# Target_board.net
KiCad netlist of a schematic drawn in EAGLE
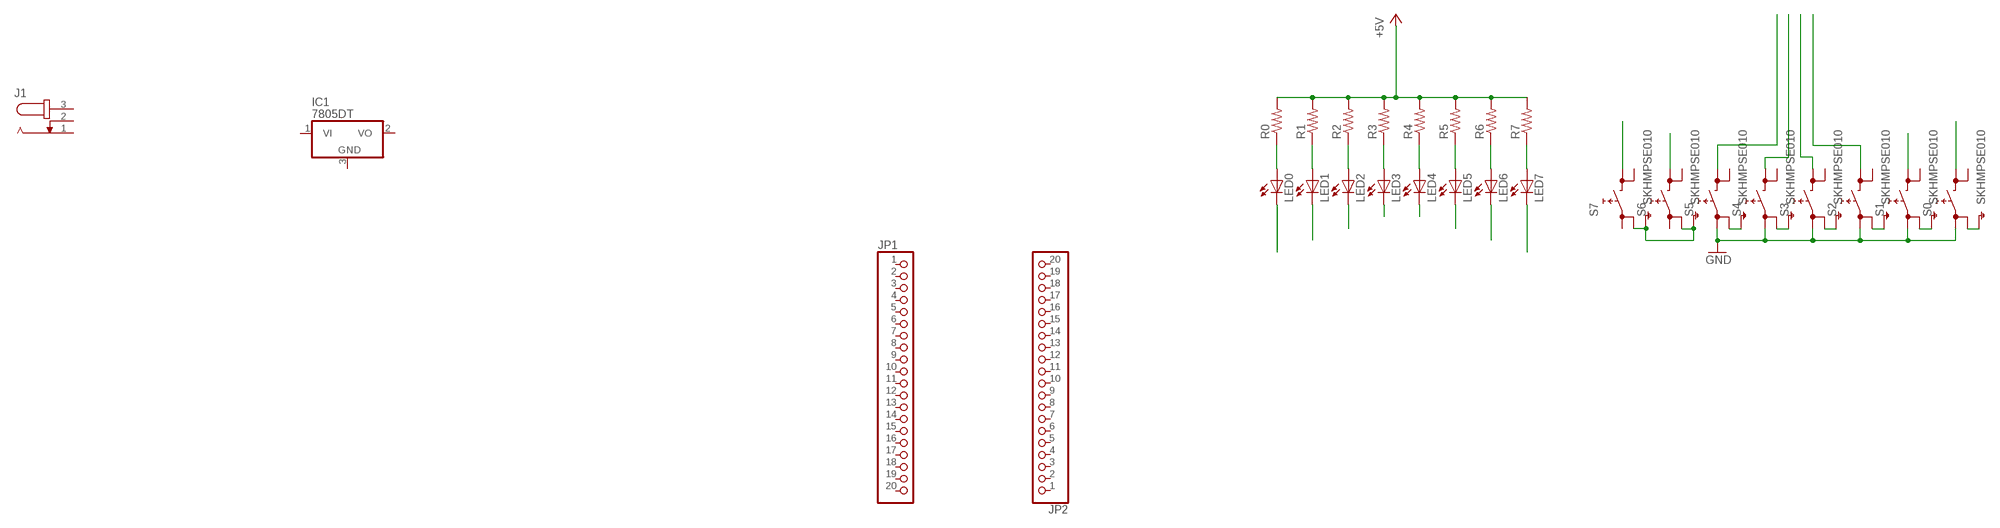
[diagram p0: schematic, sheet 1]

(export (version "E")
  (design (tool "Eeschema 10.0.6"))
  (components
    (comp (ref "IC1")
      (value "7805DT")
      (footprint "eagle-import:TO252")
      (libsource (lib "eagle-import") (part "78DT05"))
    )
    (comp (ref "J1")
      (value "JACK-PLUG0")
      (footprint "eagle-import:SPC4077")
      (libsource (lib "eagle-import") (part "JACK-PLUG0"))
    )
    (comp (ref "JP1")
      (value "PINHD-1X20")
      (footprint "eagle-import:1X20")
      (libsource (lib "eagle-import") (part "PINHD-1X20"))
    )
    (comp (ref "JP2")
      (value "PINHD-1X20")
      (footprint "eagle-import:1X20")
      (libsource (lib "eagle-import") (part "PINHD-1X20"))
    )
    (comp (ref "LED0")
      (value "LEDCHIP-LED0805")
      (footprint "eagle-import:CHIP-LED0805")
      (libsource (lib "eagle-import") (part "LEDCHIP-LED0805"))
    )
    (comp (ref "LED1")
      (value "LEDCHIP-LED0805")
      (footprint "eagle-import:CHIP-LED0805")
      (libsource (lib "eagle-import") (part "LEDCHIP-LED0805"))
    )
    (comp (ref "LED2")
      (value "LEDCHIP-LED0805")
      (footprint "eagle-import:CHIP-LED0805")
      (libsource (lib "eagle-import") (part "LEDCHIP-LED0805"))
    )
    (comp (ref "LED3")
      (value "LEDCHIP-LED0805")
      (footprint "eagle-import:CHIP-LED0805")
      (libsource (lib "eagle-import") (part "LEDCHIP-LED0805"))
    )
    (comp (ref "LED4")
      (value "LEDCHIP-LED0805")
      (footprint "eagle-import:CHIP-LED0805")
      (libsource (lib "eagle-import") (part "LEDCHIP-LED0805"))
    )
    (comp (ref "LED5")
      (value "LEDCHIP-LED0805")
      (footprint "eagle-import:CHIP-LED0805")
      (libsource (lib "eagle-import") (part "LEDCHIP-LED0805"))
    )
    (comp (ref "LED6")
      (value "LEDCHIP-LED0805")
      (footprint "eagle-import:CHIP-LED0805")
      (libsource (lib "eagle-import") (part "LEDCHIP-LED0805"))
    )
    (comp (ref "LED7")
      (value "LEDCHIP-LED0805")
      (footprint "eagle-import:CHIP-LED0805")
      (libsource (lib "eagle-import") (part "LEDCHIP-LED0805"))
    )
    (comp (ref "R0")
      (value "R-US_R0805")
      (footprint "eagle-import:R0805")
      (libsource (lib "eagle-import") (part "R-US_R0805"))
    )
    (comp (ref "R1")
      (value "R-US_R0805")
      (footprint "eagle-import:R0805")
      (libsource (lib "eagle-import") (part "R-US_R0805"))
    )
    (comp (ref "R2")
      (value "R-US_R0805")
      (footprint "eagle-import:R0805")
      (libsource (lib "eagle-import") (part "R-US_R0805"))
    )
    (comp (ref "R3")
      (value "R-US_R0805")
      (footprint "eagle-import:R0805")
      (libsource (lib "eagle-import") (part "R-US_R0805"))
    )
    (comp (ref "R4")
      (value "R-US_R0805")
      (footprint "eagle-import:R0805")
      (libsource (lib "eagle-import") (part "R-US_R0805"))
    )
    (comp (ref "R5")
      (value "R-US_R0805")
      (footprint "eagle-import:R0805")
      (libsource (lib "eagle-import") (part "R-US_R0805"))
    )
    (comp (ref "R6")
      (value "R-US_R0805")
      (footprint "eagle-import:R0805")
      (libsource (lib "eagle-import") (part "R-US_R0805"))
    )
    (comp (ref "R7")
      (value "R-US_R0805")
      (footprint "eagle-import:R0805")
      (libsource (lib "eagle-import") (part "R-US_R0805"))
    )
    (comp (ref "S0")
      (value "SKHMPSE010")
      (footprint "eagle-import:SKHMPXE010")
      (libsource (lib "eagle-import") (part "SKHMPE010S"))
    )
    (comp (ref "S1")
      (value "SKHMPSE010")
      (footprint "eagle-import:SKHMPXE010")
      (libsource (lib "eagle-import") (part "SKHMPE010S"))
    )
    (comp (ref "S2")
      (value "SKHMPSE010")
      (footprint "eagle-import:SKHMPXE010")
      (libsource (lib "eagle-import") (part "SKHMPE010S"))
    )
    (comp (ref "S3")
      (value "SKHMPSE010")
      (footprint "eagle-import:SKHMPXE010")
      (libsource (lib "eagle-import") (part "SKHMPE010S"))
    )
    (comp (ref "S4")
      (value "SKHMPSE010")
      (footprint "eagle-import:SKHMPXE010")
      (libsource (lib "eagle-import") (part "SKHMPE010S"))
    )
    (comp (ref "S5")
      (value "SKHMPSE010")
      (footprint "eagle-import:SKHMPXE010")
      (libsource (lib "eagle-import") (part "SKHMPE010S"))
    )
    (comp (ref "S6")
      (value "SKHMPSE010")
      (footprint "eagle-import:SKHMPXE010")
      (libsource (lib "eagle-import") (part "SKHMPE010S"))
    )
    (comp (ref "S7")
      (value "SKHMPSE010")
      (footprint "eagle-import:SKHMPXE010")
      (libsource (lib "eagle-import") (part "SKHMPE010S"))
    )
  )
  (nets
    (net (code "1") (name "+5V") (class "Default")
      (node (ref "R0") (pin "2") (pinfunction "2_2") (pintype "passive"))
      (node (ref "R1") (pin "2") (pinfunction "2_2") (pintype "passive"))
      (node (ref "R2") (pin "2") (pinfunction "2_2") (pintype "passive"))
      (node (ref "R3") (pin "2") (pinfunction "2_2") (pintype "passive"))
      (node (ref "R4") (pin "2") (pinfunction "2_2") (pintype "passive"))
      (node (ref "R5") (pin "2") (pinfunction "2_2") (pintype "passive"))
      (node (ref "R6") (pin "2") (pinfunction "2_2") (pintype "passive"))
      (node (ref "R7") (pin "2") (pinfunction "2_2") (pintype "passive"))
    )
    (net (code "2") (name "GND") (class "Default")
      (node (ref "S0") (pin "1") (pinfunction "1.1_1") (pintype "passive"))
      (node (ref "S1") (pin "1") (pinfunction "1.1_1") (pintype "passive"))
      (node (ref "S2") (pin "1") (pinfunction "1.1_1") (pintype "passive"))
      (node (ref "S3") (pin "1") (pinfunction "1.1_1") (pintype "passive"))
      (node (ref "S4") (pin "1") (pinfunction "1.1_1") (pintype "passive"))
      (node (ref "S5") (pin "1") (pinfunction "1.1_1") (pintype "passive"))
    )
    (net (code "3") (name "Net-(LED0-PadA)") (class "Default")
      (node (ref "LED0") (pin "A") (pinfunction "A_A") (pintype "passive"))
      (node (ref "R0") (pin "1") (pinfunction "1_1") (pintype "passive"))
    )
    (net (code "4") (name "Net-(LED1-PadA)") (class "Default")
      (node (ref "LED1") (pin "A") (pinfunction "A_A") (pintype "passive"))
      (node (ref "R1") (pin "1") (pinfunction "1_1") (pintype "passive"))
    )
    (net (code "5") (name "Net-(LED2-PadA)") (class "Default")
      (node (ref "LED2") (pin "A") (pinfunction "A_A") (pintype "passive"))
      (node (ref "R2") (pin "1") (pinfunction "1_1") (pintype "passive"))
    )
    (net (code "6") (name "Net-(LED3-PadA)") (class "Default")
      (node (ref "LED3") (pin "A") (pinfunction "A_A") (pintype "passive"))
      (node (ref "R3") (pin "1") (pinfunction "1_1") (pintype "passive"))
    )
    (net (code "7") (name "Net-(LED4-PadA)") (class "Default")
      (node (ref "LED4") (pin "A") (pinfunction "A_A") (pintype "passive"))
      (node (ref "R4") (pin "1") (pinfunction "1_1") (pintype "passive"))
    )
    (net (code "8") (name "Net-(LED5-PadA)") (class "Default")
      (node (ref "LED5") (pin "A") (pinfunction "A_A") (pintype "passive"))
      (node (ref "R5") (pin "1") (pinfunction "1_1") (pintype "passive"))
    )
    (net (code "9") (name "Net-(LED6-PadA)") (class "Default")
      (node (ref "LED6") (pin "A") (pinfunction "A_A") (pintype "passive"))
      (node (ref "R6") (pin "1") (pinfunction "1_1") (pintype "passive"))
    )
    (net (code "10") (name "Net-(LED7-PadA)") (class "Default")
      (node (ref "LED7") (pin "A") (pinfunction "A_A") (pintype "passive"))
      (node (ref "R7") (pin "1") (pinfunction "1_1") (pintype "passive"))
    )
    (net (code "11") (name "Net-(S0-1.2)") (class "Default")
      (node (ref "S0") (pin "2") (pinfunction "1.2_2") (pintype "passive"))
      (node (ref "S0") (pin "5") (pinfunction "SH_5") (pintype "passive"))
    )
    (net (code "12") (name "Net-(S1-1.2)") (class "Default")
      (node (ref "S1") (pin "2") (pinfunction "1.2_2") (pintype "passive"))
      (node (ref "S1") (pin "5") (pinfunction "SH_5") (pintype "passive"))
    )
    (net (code "13") (name "Net-(S2-1.2)") (class "Default")
      (node (ref "S2") (pin "2") (pinfunction "1.2_2") (pintype "passive"))
      (node (ref "S2") (pin "5") (pinfunction "SH_5") (pintype "passive"))
    )
    (net (code "14") (name "Net-(S3-1.2)") (class "Default")
      (node (ref "S3") (pin "2") (pinfunction "1.2_2") (pintype "passive"))
      (node (ref "S3") (pin "5") (pinfunction "SH_5") (pintype "passive"))
    )
    (net (code "15") (name "Net-(S4-1.2)") (class "Default")
      (node (ref "S4") (pin "2") (pinfunction "1.2_2") (pintype "passive"))
      (node (ref "S4") (pin "5") (pinfunction "SH_5") (pintype "passive"))
    )
    (net (code "16") (name "Net-(S5-1.2)") (class "Default")
      (node (ref "S5") (pin "2") (pinfunction "1.2_2") (pintype "passive"))
      (node (ref "S5") (pin "5") (pinfunction "SH_5") (pintype "passive"))
    )
    (net (code "17") (name "Net-(S6-1.2)") (class "Default")
      (node (ref "S6") (pin "2") (pinfunction "1.2_2") (pintype "passive"))
      (node (ref "S6") (pin "5") (pinfunction "SH_5") (pintype "passive"))
      (node (ref "S7") (pin "2") (pinfunction "1.2_2") (pintype "passive"))
      (node (ref "S7") (pin "5") (pinfunction "SH_5") (pintype "passive"))
    )
    (net (code "18") (name "unconnected-(IC1-GND-Pad3)") (class "Default")
      (node (ref "IC1") (pin "3") (pinfunction "GND_3") (pintype "passive"))
    )
    (net (code "19") (name "unconnected-(IC1-VI-Pad1)") (class "Default")
      (node (ref "IC1") (pin "1") (pinfunction "VI_1") (pintype "input"))
    )
    (net (code "20") (name "unconnected-(IC1-VO-Pad2)") (class "Default")
      (node (ref "IC1") (pin "2") (pinfunction "VO_2") (pintype "passive"))
    )
    (net (code "21") (name "unconnected-(J1-Pad1)") (class "Default")
      (node (ref "J1") (pin "1") (pinfunction "1_1") (pintype "passive"))
    )
    (net (code "22") (name "unconnected-(J1-Pad2)") (class "Default")
      (node (ref "J1") (pin "2") (pinfunction "2_2") (pintype "passive"))
    )
    (net (code "23") (name "unconnected-(J1-Pad3)") (class "Default")
      (node (ref "J1") (pin "3") (pinfunction "3_3") (pintype "passive"))
    )
    (net (code "24") (name "unconnected-(JP1-Pad1)") (class "Default")
      (node (ref "JP1") (pin "1") (pinfunction "1_1") (pintype "passive"))
    )
    (net (code "25") (name "unconnected-(JP1-Pad2)") (class "Default")
      (node (ref "JP1") (pin "2") (pinfunction "2_2") (pintype "passive"))
    )
    (net (code "26") (name "unconnected-(JP1-Pad3)") (class "Default")
      (node (ref "JP1") (pin "3") (pinfunction "3_3") (pintype "passive"))
    )
    (net (code "27") (name "unconnected-(JP1-Pad4)") (class "Default")
      (node (ref "JP1") (pin "4") (pinfunction "4_4") (pintype "passive"))
    )
    (net (code "28") (name "unconnected-(JP1-Pad5)") (class "Default")
      (node (ref "JP1") (pin "5") (pinfunction "5_5") (pintype "passive"))
    )
    (net (code "29") (name "unconnected-(JP1-Pad6)") (class "Default")
      (node (ref "JP1") (pin "6") (pinfunction "6_6") (pintype "passive"))
    )
    (net (code "30") (name "unconnected-(JP1-Pad7)") (class "Default")
      (node (ref "JP1") (pin "7") (pinfunction "7_7") (pintype "passive"))
    )
    (net (code "31") (name "unconnected-(JP1-Pad8)") (class "Default")
      (node (ref "JP1") (pin "8") (pinfunction "8_8") (pintype "passive"))
    )
    (net (code "32") (name "unconnected-(JP1-Pad9)") (class "Default")
      (node (ref "JP1") (pin "9") (pinfunction "9_9") (pintype "passive"))
    )
    (net (code "33") (name "unconnected-(JP1-Pad10)") (class "Default")
      (node (ref "JP1") (pin "10") (pinfunction "10_10") (pintype "passive"))
    )
    (net (code "34") (name "unconnected-(JP1-Pad11)") (class "Default")
      (node (ref "JP1") (pin "11") (pinfunction "11_11") (pintype "passive"))
    )
    (net (code "35") (name "unconnected-(JP1-Pad12)") (class "Default")
      (node (ref "JP1") (pin "12") (pinfunction "12_12") (pintype "passive"))
    )
    (net (code "36") (name "unconnected-(JP1-Pad13)") (class "Default")
      (node (ref "JP1") (pin "13") (pinfunction "13_13") (pintype "passive"))
    )
    (net (code "37") (name "unconnected-(JP1-Pad14)") (class "Default")
      (node (ref "JP1") (pin "14") (pinfunction "14_14") (pintype "passive"))
    )
    (net (code "38") (name "unconnected-(JP1-Pad15)") (class "Default")
      (node (ref "JP1") (pin "15") (pinfunction "15_15") (pintype "passive"))
    )
    (net (code "39") (name "unconnected-(JP1-Pad16)") (class "Default")
      (node (ref "JP1") (pin "16") (pinfunction "16_16") (pintype "passive"))
    )
    (net (code "40") (name "unconnected-(JP1-Pad17)") (class "Default")
      (node (ref "JP1") (pin "17") (pinfunction "17_17") (pintype "passive"))
    )
    (net (code "41") (name "unconnected-(JP1-Pad18)") (class "Default")
      (node (ref "JP1") (pin "18") (pinfunction "18_18") (pintype "passive"))
    )
    (net (code "42") (name "unconnected-(JP1-Pad19)") (class "Default")
      (node (ref "JP1") (pin "19") (pinfunction "19_19") (pintype "passive"))
    )
    (net (code "43") (name "unconnected-(JP1-Pad20)") (class "Default")
      (node (ref "JP1") (pin "20") (pinfunction "20_20") (pintype "passive"))
    )
    (net (code "44") (name "unconnected-(JP2-Pad1)") (class "Default")
      (node (ref "JP2") (pin "1") (pinfunction "1_1") (pintype "passive"))
    )
    (net (code "45") (name "unconnected-(JP2-Pad2)") (class "Default")
      (node (ref "JP2") (pin "2") (pinfunction "2_2") (pintype "passive"))
    )
    (net (code "46") (name "unconnected-(JP2-Pad3)") (class "Default")
      (node (ref "JP2") (pin "3") (pinfunction "3_3") (pintype "passive"))
    )
    (net (code "47") (name "unconnected-(JP2-Pad4)") (class "Default")
      (node (ref "JP2") (pin "4") (pinfunction "4_4") (pintype "passive"))
    )
    (net (code "48") (name "unconnected-(JP2-Pad5)") (class "Default")
      (node (ref "JP2") (pin "5") (pinfunction "5_5") (pintype "passive"))
    )
    (net (code "49") (name "unconnected-(JP2-Pad6)") (class "Default")
      (node (ref "JP2") (pin "6") (pinfunction "6_6") (pintype "passive"))
    )
    (net (code "50") (name "unconnected-(JP2-Pad7)") (class "Default")
      (node (ref "JP2") (pin "7") (pinfunction "7_7") (pintype "passive"))
    )
    (net (code "51") (name "unconnected-(JP2-Pad8)") (class "Default")
      (node (ref "JP2") (pin "8") (pinfunction "8_8") (pintype "passive"))
    )
    (net (code "52") (name "unconnected-(JP2-Pad9)") (class "Default")
      (node (ref "JP2") (pin "9") (pinfunction "9_9") (pintype "passive"))
    )
    (net (code "53") (name "unconnected-(JP2-Pad10)") (class "Default")
      (node (ref "JP2") (pin "10") (pinfunction "10_10") (pintype "passive"))
    )
    (net (code "54") (name "unconnected-(JP2-Pad11)") (class "Default")
      (node (ref "JP2") (pin "11") (pinfunction "11_11") (pintype "passive"))
    )
    (net (code "55") (name "unconnected-(JP2-Pad12)") (class "Default")
      (node (ref "JP2") (pin "12") (pinfunction "12_12") (pintype "passive"))
    )
    (net (code "56") (name "unconnected-(JP2-Pad13)") (class "Default")
      (node (ref "JP2") (pin "13") (pinfunction "13_13") (pintype "passive"))
    )
    (net (code "57") (name "unconnected-(JP2-Pad14)") (class "Default")
      (node (ref "JP2") (pin "14") (pinfunction "14_14") (pintype "passive"))
    )
    (net (code "58") (name "unconnected-(JP2-Pad15)") (class "Default")
      (node (ref "JP2") (pin "15") (pinfunction "15_15") (pintype "passive"))
    )
    (net (code "59") (name "unconnected-(JP2-Pad16)") (class "Default")
      (node (ref "JP2") (pin "16") (pinfunction "16_16") (pintype "passive"))
    )
    (net (code "60") (name "unconnected-(JP2-Pad17)") (class "Default")
      (node (ref "JP2") (pin "17") (pinfunction "17_17") (pintype "passive"))
    )
    (net (code "61") (name "unconnected-(JP2-Pad18)") (class "Default")
      (node (ref "JP2") (pin "18") (pinfunction "18_18") (pintype "passive"))
    )
    (net (code "62") (name "unconnected-(JP2-Pad19)") (class "Default")
      (node (ref "JP2") (pin "19") (pinfunction "19_19") (pintype "passive"))
    )
    (net (code "63") (name "unconnected-(JP2-Pad20)") (class "Default")
      (node (ref "JP2") (pin "20") (pinfunction "20_20") (pintype "passive"))
    )
    (net (code "64") (name "unconnected-(LED0-PadC)") (class "Default")
      (node (ref "LED0") (pin "C") (pinfunction "C_C") (pintype "passive"))
    )
    (net (code "65") (name "unconnected-(LED1-PadC)") (class "Default")
      (node (ref "LED1") (pin "C") (pinfunction "C_C") (pintype "passive"))
    )
    (net (code "66") (name "unconnected-(LED2-PadC)") (class "Default")
      (node (ref "LED2") (pin "C") (pinfunction "C_C") (pintype "passive"))
    )
    (net (code "67") (name "unconnected-(LED3-PadC)") (class "Default")
      (node (ref "LED3") (pin "C") (pinfunction "C_C") (pintype "passive"))
    )
    (net (code "68") (name "unconnected-(LED4-PadC)") (class "Default")
      (node (ref "LED4") (pin "C") (pinfunction "C_C") (pintype "passive"))
    )
    (net (code "69") (name "unconnected-(LED5-PadC)") (class "Default")
      (node (ref "LED5") (pin "C") (pinfunction "C_C") (pintype "passive"))
    )
    (net (code "70") (name "unconnected-(LED6-PadC)") (class "Default")
      (node (ref "LED6") (pin "C") (pinfunction "C_C") (pintype "passive"))
    )
    (net (code "71") (name "unconnected-(LED7-PadC)") (class "Default")
      (node (ref "LED7") (pin "C") (pinfunction "C_C") (pintype "passive"))
    )
    (net (code "72") (name "unconnected-(S0-2.1-Pad3)") (class "Default")
      (node (ref "S0") (pin "3") (pinfunction "2.1_3") (pintype "passive"))
    )
    (net (code "73") (name "unconnected-(S0-2.2-Pad4)") (class "Default")
      (node (ref "S0") (pin "4") (pinfunction "2.2_4") (pintype "passive"))
    )
    (net (code "74") (name "unconnected-(S1-2.1-Pad3)") (class "Default")
      (node (ref "S1") (pin "3") (pinfunction "2.1_3") (pintype "passive"))
    )
    (net (code "75") (name "unconnected-(S1-2.2-Pad4)") (class "Default")
      (node (ref "S1") (pin "4") (pinfunction "2.2_4") (pintype "passive"))
    )
    (net (code "76") (name "unconnected-(S2-2.1-Pad3)") (class "Default")
      (node (ref "S2") (pin "3") (pinfunction "2.1_3") (pintype "passive"))
    )
    (net (code "77") (name "unconnected-(S2-2.2-Pad4)") (class "Default")
      (node (ref "S2") (pin "4") (pinfunction "2.2_4") (pintype "passive"))
    )
    (net (code "78") (name "unconnected-(S3-2.1-Pad3)") (class "Default")
      (node (ref "S3") (pin "3") (pinfunction "2.1_3") (pintype "passive"))
    )
    (net (code "79") (name "unconnected-(S3-2.2-Pad4)") (class "Default")
      (node (ref "S3") (pin "4") (pinfunction "2.2_4") (pintype "passive"))
    )
    (net (code "80") (name "unconnected-(S4-2.1-Pad3)") (class "Default")
      (node (ref "S4") (pin "3") (pinfunction "2.1_3") (pintype "passive"))
    )
    (net (code "81") (name "unconnected-(S4-2.2-Pad4)") (class "Default")
      (node (ref "S4") (pin "4") (pinfunction "2.2_4") (pintype "passive"))
    )
    (net (code "82") (name "unconnected-(S5-2.1-Pad3)") (class "Default")
      (node (ref "S5") (pin "3") (pinfunction "2.1_3") (pintype "passive"))
    )
    (net (code "83") (name "unconnected-(S5-2.2-Pad4)") (class "Default")
      (node (ref "S5") (pin "4") (pinfunction "2.2_4") (pintype "passive"))
    )
    (net (code "84") (name "unconnected-(S6-1.1-Pad1)") (class "Default")
      (node (ref "S6") (pin "1") (pinfunction "1.1_1") (pintype "passive"))
    )
    (net (code "85") (name "unconnected-(S6-2.1-Pad3)") (class "Default")
      (node (ref "S6") (pin "3") (pinfunction "2.1_3") (pintype "passive"))
    )
    (net (code "86") (name "unconnected-(S6-2.2-Pad4)") (class "Default")
      (node (ref "S6") (pin "4") (pinfunction "2.2_4") (pintype "passive"))
    )
    (net (code "87") (name "unconnected-(S7-1.1-Pad1)") (class "Default")
      (node (ref "S7") (pin "1") (pinfunction "1.1_1") (pintype "passive"))
    )
    (net (code "88") (name "unconnected-(S7-2.1-Pad3)") (class "Default")
      (node (ref "S7") (pin "3") (pinfunction "2.1_3") (pintype "passive"))
    )
    (net (code "89") (name "unconnected-(S7-2.2-Pad4)") (class "Default")
      (node (ref "S7") (pin "4") (pinfunction "2.2_4") (pintype "passive"))
    )
  )
)
